# Weather_Box.net
KiCad netlist of a schematic drawn in EAGLE
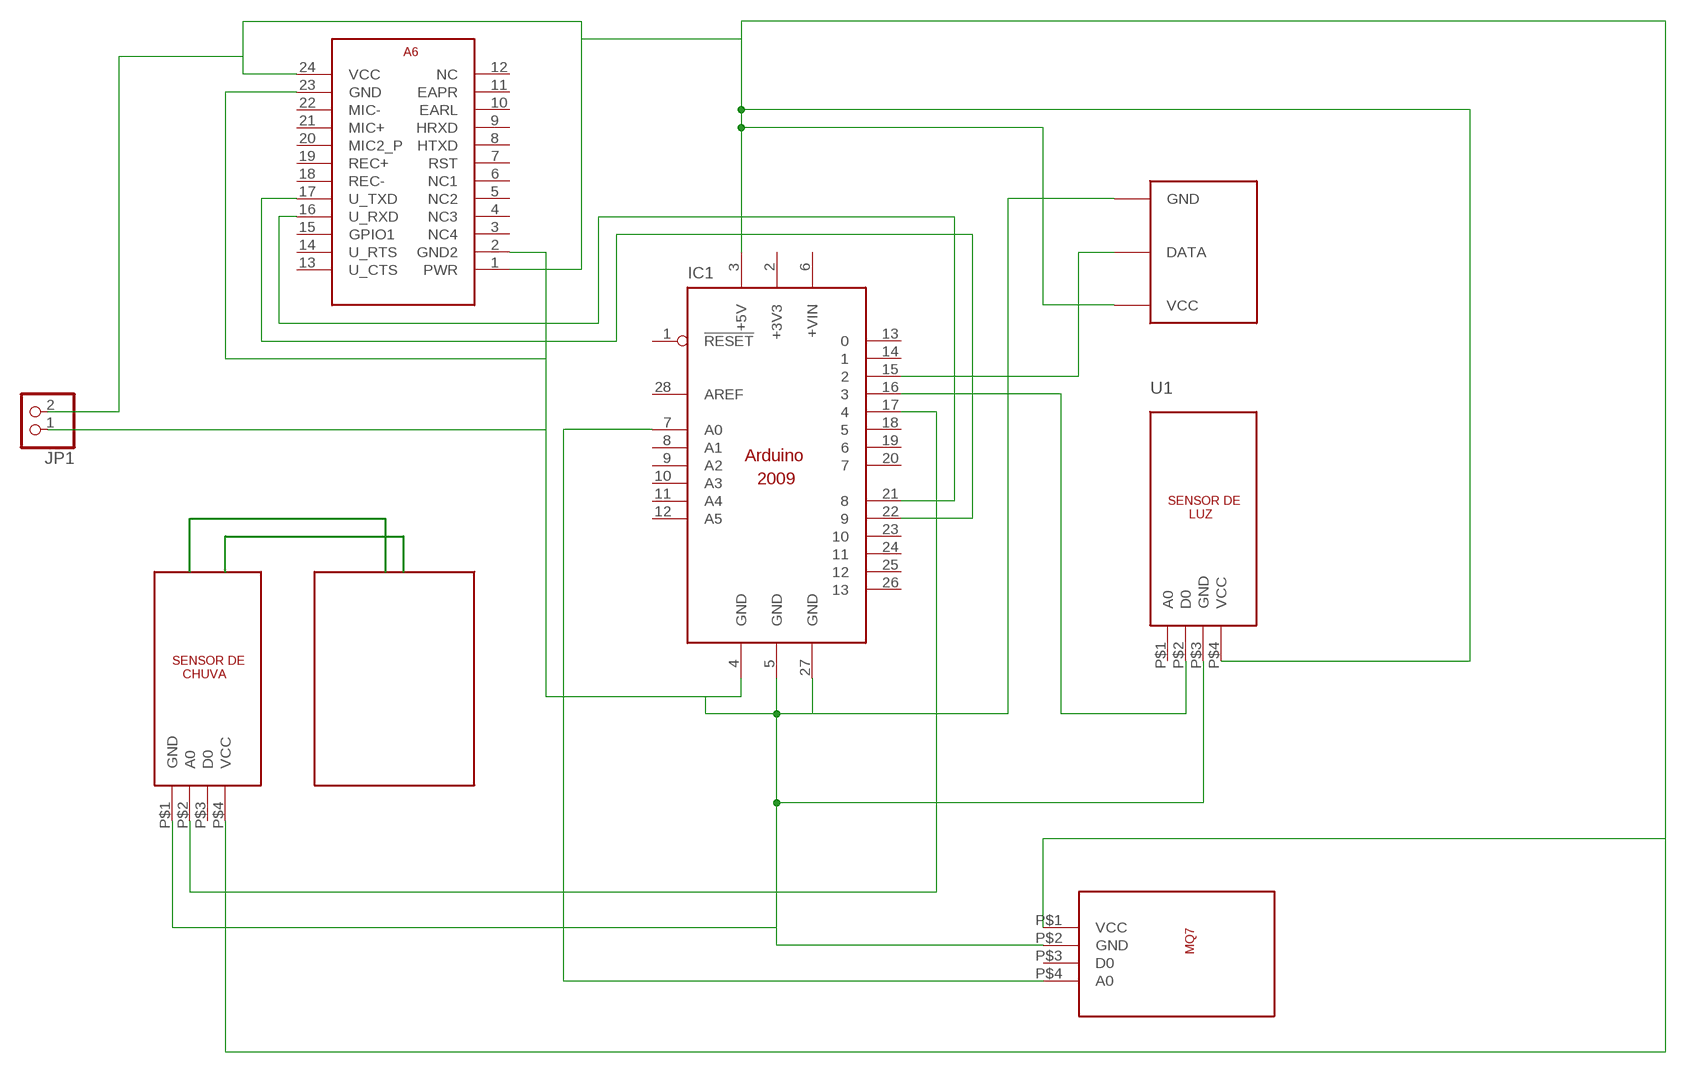
[diagram p0: schematic, sheet 1]

(export (version "E")
  (design (tool "Eeschema 10.0.6"))
  (components
    (comp (ref "IC1")
      (value "ARDUINO2009_10")
      (footprint "eagle-import:ARDUINO2009")
      (libsource (lib "eagle-import") (part "ARDUINO2009_10"))
    )
    (comp (ref "JP1")
      (value "PINHD-1X2")
      (footprint "eagle-import:1X02")
      (libsource (lib "eagle-import") (part "PINHD-1X2"))
    )
    (comp (ref "SHT1")
      (value "DHT11DHT11-UPRIGHT")
      (footprint "eagle-import:DHT11-UP")
      (libsource (lib "eagle-import") (part "DHT11DHT11-UPRIGHT"))
    )
    (comp (ref "U1")
      (value "LDRLDR-UPRIGHT")
      (footprint "eagle-import:LDR-UP")
      (libsource (lib "eagle-import") (part "LDRLDR-UPRIGHT"))
    )
    (comp (ref "U2")
      (value "A6GPRS")
      (footprint "eagle-import:A6_MODULE_V3")
      (libsource (lib "eagle-import") (part "A6GPRS"))
    )
    (comp (ref "U3")
      (value "RAINLDR-UPRIGHT")
      (footprint "eagle-import:RAIN-UP")
      (libsource (lib "eagle-import") (part "RAINLDR-UPRIGHT"))
    )
    (comp (ref "U4")
      (value "MQ7MQ7-UPRIGHT")
      (footprint "eagle-import:MQ7-UP")
      (libsource (lib "eagle-import") (part "MQ7MQ7-UPRIGHT"))
    )
  )
  (nets
    (net (code "1") (name "/+3V3") (class "Default")
      (node (ref "IC1") (pin "2") (pinfunction "+3V3_2") (pintype "power_in"))
    )
    (net (code "2") (name "Net-(IC1-+5V)") (class "Default")
      (node (ref "IC1") (pin "3") (pinfunction "+5V_3") (pintype "power_in"))
      (node (ref "JP1") (pin "2") (pinfunction "2_2") (pintype "passive"))
      (node (ref "SHT1") (pin "P$1") (pinfunction "VCC_P$1") (pintype "power_in"))
      (node (ref "U1") (pin "P$4") (pinfunction "VCC_P$4") (pintype "bidirectional"))
      (node (ref "U2") (pin "1") (pinfunction "PWR_1") (pintype "bidirectional"))
      (node (ref "U2") (pin "24") (pinfunction "VCC_24") (pintype "bidirectional"))
      (node (ref "U3") (pin "P$4") (pinfunction "VCC_P$4") (pintype "bidirectional"))
      (node (ref "U4") (pin "P$1") (pinfunction "VCC_P$1") (pintype "bidirectional"))
    )
    (net (code "3") (name "Net-(IC1-2)") (class "Default")
      (node (ref "IC1") (pin "15") (pinfunction "2_15") (pintype "bidirectional"))
      (node (ref "SHT1") (pin "P$3") (pinfunction "DATA_P$3") (pintype "bidirectional"))
    )
    (net (code "4") (name "Net-(IC1-3)") (class "Default")
      (node (ref "IC1") (pin "16") (pinfunction "3_16") (pintype "bidirectional"))
      (node (ref "U1") (pin "P$2") (pinfunction "D0_P$2") (pintype "bidirectional"))
    )
    (net (code "5") (name "Net-(IC1-4)") (class "Default")
      (node (ref "IC1") (pin "17") (pinfunction "4_17") (pintype "bidirectional"))
      (node (ref "U3") (pin "P$2") (pinfunction "A0_P$2") (pintype "bidirectional"))
    )
    (net (code "6") (name "Net-(IC1-8)") (class "Default")
      (node (ref "IC1") (pin "21") (pinfunction "8_21") (pintype "bidirectional"))
      (node (ref "U2") (pin "16") (pinfunction "U_RXD_16") (pintype "bidirectional"))
    )
    (net (code "7") (name "Net-(IC1-9)") (class "Default")
      (node (ref "IC1") (pin "22") (pinfunction "9_22") (pintype "bidirectional"))
      (node (ref "U2") (pin "17") (pinfunction "U_TXD_17") (pintype "bidirectional"))
    )
    (net (code "8") (name "Net-(IC1-A0)") (class "Default")
      (node (ref "IC1") (pin "7") (pinfunction "A0_7") (pintype "bidirectional"))
      (node (ref "U4") (pin "P$4") (pinfunction "A0_P$4") (pintype "bidirectional"))
    )
    (net (code "9") (name "Net-(SHT1-GND)") (class "Default")
      (node (ref "IC1") (pin "27") (pinfunction "GND_27") (pintype "power_in"))
      (node (ref "IC1") (pin "4") (pinfunction "GND_4") (pintype "power_in"))
      (node (ref "IC1") (pin "5") (pinfunction "GND_5") (pintype "power_in"))
      (node (ref "JP1") (pin "1") (pinfunction "1_1") (pintype "passive"))
      (node (ref "SHT1") (pin "P$4") (pinfunction "GND_P$4") (pintype "power_in"))
      (node (ref "U1") (pin "P$3") (pinfunction "GND_P$3") (pintype "bidirectional"))
      (node (ref "U2") (pin "2") (pinfunction "GND2_2") (pintype "bidirectional"))
      (node (ref "U2") (pin "23") (pinfunction "GND_23") (pintype "bidirectional"))
      (node (ref "U3") (pin "P$1") (pinfunction "GND_P$1") (pintype "bidirectional"))
      (node (ref "U4") (pin "P$2") (pinfunction "GND_P$2") (pintype "bidirectional"))
    )
    (net (code "10") (name "unconnected-(IC1-+VIN-Pad6)") (class "Default")
      (node (ref "IC1") (pin "6") (pinfunction "+VIN_6") (pintype "bidirectional"))
    )
    (net (code "11") (name "unconnected-(IC1-0-Pad13)") (class "Default")
      (node (ref "IC1") (pin "13") (pinfunction "0_13") (pintype "bidirectional"))
    )
    (net (code "12") (name "unconnected-(IC1-1-Pad14)") (class "Default")
      (node (ref "IC1") (pin "14") (pinfunction "1_14") (pintype "bidirectional"))
    )
    (net (code "13") (name "unconnected-(IC1-5-Pad18)") (class "Default")
      (node (ref "IC1") (pin "18") (pinfunction "5_18") (pintype "bidirectional"))
    )
    (net (code "14") (name "unconnected-(IC1-6-Pad19)") (class "Default")
      (node (ref "IC1") (pin "19") (pinfunction "6_19") (pintype "bidirectional"))
    )
    (net (code "15") (name "unconnected-(IC1-7-Pad20)") (class "Default")
      (node (ref "IC1") (pin "20") (pinfunction "7_20") (pintype "bidirectional"))
    )
    (net (code "16") (name "unconnected-(IC1-10-Pad23)") (class "Default")
      (node (ref "IC1") (pin "23") (pinfunction "10_23") (pintype "bidirectional"))
    )
    (net (code "17") (name "unconnected-(IC1-11-Pad24)") (class "Default")
      (node (ref "IC1") (pin "24") (pinfunction "11_24") (pintype "bidirectional"))
    )
    (net (code "18") (name "unconnected-(IC1-12-Pad25)") (class "Default")
      (node (ref "IC1") (pin "25") (pinfunction "12_25") (pintype "bidirectional"))
    )
    (net (code "19") (name "unconnected-(IC1-13-Pad26)") (class "Default")
      (node (ref "IC1") (pin "26") (pinfunction "13_26") (pintype "bidirectional"))
    )
    (net (code "20") (name "unconnected-(IC1-A1-Pad8)") (class "Default")
      (node (ref "IC1") (pin "8") (pinfunction "A1_8") (pintype "bidirectional"))
    )
    (net (code "21") (name "unconnected-(IC1-A2-Pad9)") (class "Default")
      (node (ref "IC1") (pin "9") (pinfunction "A2_9") (pintype "bidirectional"))
    )
    (net (code "22") (name "unconnected-(IC1-A3-Pad10)") (class "Default")
      (node (ref "IC1") (pin "10") (pinfunction "A3_10") (pintype "bidirectional"))
    )
    (net (code "23") (name "unconnected-(IC1-A4-Pad11)") (class "Default")
      (node (ref "IC1") (pin "11") (pinfunction "A4_11") (pintype "bidirectional"))
    )
    (net (code "24") (name "unconnected-(IC1-A5-Pad12)") (class "Default")
      (node (ref "IC1") (pin "12") (pinfunction "A5_12") (pintype "bidirectional"))
    )
    (net (code "25") (name "unconnected-(IC1-AREF-Pad28)") (class "Default")
      (node (ref "IC1") (pin "28") (pinfunction "AREF_28") (pintype "bidirectional"))
    )
    (net (code "26") (name "unconnected-(IC1-~{RESET}-Pad1)") (class "Default")
      (node (ref "IC1") (pin "1") (pinfunction "~{RESET}_1") (pintype "bidirectional"))
    )
    (net (code "27") (name "unconnected-(U1-A0-PadP$1)") (class "Default")
      (node (ref "U1") (pin "P$1") (pinfunction "A0_P$1") (pintype "bidirectional"))
    )
    (net (code "28") (name "unconnected-(U2-EAPR-Pad11)") (class "Default")
      (node (ref "U2") (pin "11") (pinfunction "EAPR_11") (pintype "bidirectional"))
    )
    (net (code "29") (name "unconnected-(U2-EARL-Pad10)") (class "Default")
      (node (ref "U2") (pin "10") (pinfunction "EARL_10") (pintype "bidirectional"))
    )
    (net (code "30") (name "unconnected-(U2-GPIO1-Pad15)") (class "Default")
      (node (ref "U2") (pin "15") (pinfunction "GPIO1_15") (pintype "bidirectional"))
    )
    (net (code "31") (name "unconnected-(U2-HRXD-Pad9)") (class "Default")
      (node (ref "U2") (pin "9") (pinfunction "HRXD_9") (pintype "bidirectional"))
    )
    (net (code "32") (name "unconnected-(U2-HTXD-Pad8)") (class "Default")
      (node (ref "U2") (pin "8") (pinfunction "HTXD_8") (pintype "bidirectional"))
    )
    (net (code "33") (name "unconnected-(U2-MIC+-Pad21)") (class "Default")
      (node (ref "U2") (pin "21") (pinfunction "MIC+_21") (pintype "bidirectional"))
    )
    (net (code "34") (name "unconnected-(U2-MIC--Pad22)") (class "Default")
      (node (ref "U2") (pin "22") (pinfunction "MIC-_22") (pintype "bidirectional"))
    )
    (net (code "35") (name "unconnected-(U2-MIC2_P-Pad20)") (class "Default")
      (node (ref "U2") (pin "20") (pinfunction "MIC2_P_20") (pintype "bidirectional"))
    )
    (net (code "36") (name "unconnected-(U2-NC-Pad12)") (class "Default")
      (node (ref "U2") (pin "12") (pinfunction "NC_12") (pintype "bidirectional"))
    )
    (net (code "37") (name "unconnected-(U2-NC1-Pad6)") (class "Default")
      (node (ref "U2") (pin "6") (pinfunction "NC1_6") (pintype "bidirectional"))
    )
    (net (code "38") (name "unconnected-(U2-NC2-Pad5)") (class "Default")
      (node (ref "U2") (pin "5") (pinfunction "NC2_5") (pintype "bidirectional"))
    )
    (net (code "39") (name "unconnected-(U2-NC3-Pad4)") (class "Default")
      (node (ref "U2") (pin "4") (pinfunction "NC3_4") (pintype "bidirectional"))
    )
    (net (code "40") (name "unconnected-(U2-NC4-Pad3)") (class "Default")
      (node (ref "U2") (pin "3") (pinfunction "NC4_3") (pintype "bidirectional"))
    )
    (net (code "41") (name "unconnected-(U2-REC+-Pad19)") (class "Default")
      (node (ref "U2") (pin "19") (pinfunction "REC+_19") (pintype "bidirectional"))
    )
    (net (code "42") (name "unconnected-(U2-REC--Pad18)") (class "Default")
      (node (ref "U2") (pin "18") (pinfunction "REC-_18") (pintype "bidirectional"))
    )
    (net (code "43") (name "unconnected-(U2-RST-Pad7)") (class "Default")
      (node (ref "U2") (pin "7") (pinfunction "RST_7") (pintype "bidirectional"))
    )
    (net (code "44") (name "unconnected-(U2-U_CTS-Pad13)") (class "Default")
      (node (ref "U2") (pin "13") (pinfunction "U_CTS_13") (pintype "bidirectional"))
    )
    (net (code "45") (name "unconnected-(U2-U_RTS-Pad14)") (class "Default")
      (node (ref "U2") (pin "14") (pinfunction "U_RTS_14") (pintype "bidirectional"))
    )
    (net (code "46") (name "unconnected-(U3-D0-PadP$3)") (class "Default")
      (node (ref "U3") (pin "P$3") (pinfunction "D0_P$3") (pintype "bidirectional"))
    )
    (net (code "47") (name "unconnected-(U4-D0-PadP$3)") (class "Default")
      (node (ref "U4") (pin "P$3") (pinfunction "D0_P$3") (pintype "bidirectional"))
    )
  )
)
